# AD8307.net
KiCad netlist of a schematic drawn in Altium Designer
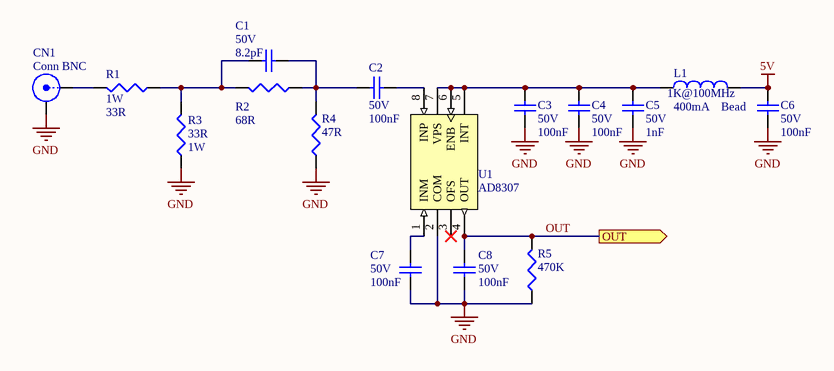
[diagram p0: AD8307.SchDoc]

(export (version "E")
  (design (tool "Eeschema 10.0.6"))
  (components
    (comp (ref "C1")
      (value "8.2pF")
      (footprint "CC0603")
      (description "Capacitor (Semiconductor SIM Model)")
      (fields (field (name "TENSÃO") "50V") (field (name "Comment") "Capacitor Cerâmico"))
      (libsource (lib "NavarroCAP") (part "Cap 8.2nF 50V 0603 X7R"))
    )
    (comp (ref "C2")
      (value "100nF")
      (footprint "CC0603")
      (description "Capacitor (Semiconductor SIM Model)")
      (fields (field (name "TENSÃO") "50V") (field (name "Comment") "Capacitor Cerâmico"))
      (libsource (lib "NavarroCAP") (part "Cap 100nF 50V 0603 X7R"))
    )
    (comp (ref "C3")
      (value "100nF")
      (footprint "CC0603")
      (description "Capacitor (Semiconductor SIM Model)")
      (fields (field (name "TENSÃO") "50V") (field (name "Comment") "Capacitor Cerâmico"))
      (libsource (lib "NavarroCAP") (part "Cap 100nF 50V 0603 X7R"))
    )
    (comp (ref "C4")
      (value "100nF")
      (footprint "CC0603")
      (description "Capacitor (Semiconductor SIM Model)")
      (fields (field (name "TENSÃO") "50V") (field (name "Comment") "Capacitor Cerâmico"))
      (libsource (lib "NavarroCAP") (part "Cap 100nF 50V 0603 X7R"))
    )
    (comp (ref "C5")
      (value "1nF")
      (footprint "CC0603")
      (description "Capacitor (Semiconductor SIM Model)")
      (fields (field (name "TENSÃO") "50V") (field (name "Comment") "Capacitor Cerâmico"))
      (libsource (lib "NavarroCAP") (part "Cap 1nF 50V 0603 X7R"))
    )
    (comp (ref "C6")
      (value "100nF")
      (footprint "CC0603")
      (description "Capacitor (Semiconductor SIM Model)")
      (fields (field (name "TENSÃO") "50V") (field (name "Comment") "Capacitor Cerâmico"))
      (libsource (lib "NavarroCAP") (part "Cap 100nF 50V 0603 X7R"))
    )
    (comp (ref "C7")
      (value "100nF")
      (footprint "CC0603")
      (description "Capacitor (Semiconductor SIM Model)")
      (fields (field (name "TENSÃO") "50V") (field (name "Comment") "Capacitor Cerâmico"))
      (libsource (lib "NavarroCAP") (part "Cap 100nF 50V 0603 X7R"))
    )
    (comp (ref "C8")
      (value "100nF")
      (footprint "CC0603")
      (description "Capacitor (Semiconductor SIM Model)")
      (fields (field (name "TENSÃO") "50V") (field (name "Comment") "Capacitor Cerâmico"))
      (libsource (lib "NavarroCAP") (part "Cap 100nF 50V 0603 X7R"))
    )
    (comp (ref "CN1")
      (value "Conn BNC")
      (footprint "CONN BNC-JACK-TE-5-1634556-0")
      (description "Conector BNC")
      (libsource (lib "TecnocladeCON") (part "Conn BNC"))
    )
    (comp (ref "L1")
      (value "Bead")
      (footprint "CC0603")
      (fields (field (name "CORRENTE") "400mA") (field (name "ALTIUM_VALUE") "1K@100MHz"))
      (libsource (lib "NavarroIND") (part "Bd 1K@100MHz 0603 400mA"))
    )
    (comp (ref "R1")
      (value "33R")
      (footprint "CC2512")
      (description "Resistor")
      (fields (field (name "POTÊNCIA") "1W"))
      (libsource (lib "NavarroRES") (part "Res 33R 1% 0603 1/10W"))
    )
    (comp (ref "R2")
      (value "68R")
      (footprint "CC0603")
      (description "Resistor")
      (libsource (lib "NavarroRES") (part "Res 1K 1% 0603 1/10W"))
    )
    (comp (ref "R3")
      (value "33R")
      (footprint "CC2512")
      (description "Resistor")
      (fields (field (name "POTÊNCIA") "1W"))
      (libsource (lib "NavarroRES") (part "Res 33R 1% 0603 1/10W"))
    )
    (comp (ref "R4")
      (value "47R")
      (footprint "CC0603")
      (description "Resistor")
      (libsource (lib "NavarroRES") (part "Res 1K 1% 0603 1/10W"))
    )
    (comp (ref "R5")
      (value "470K")
      (footprint "CC0603")
      (description "Resistor")
      (libsource (lib "NavarroRES") (part "Res 470K 1% 0603 1/10W"))
    )
    (comp (ref "U1")
      (value "AD8307")
      (footprint "SOIC-8N")
      (description "Low Cost, DC to 500 MHz, 92 dB Log Amp")
      (libsource (lib "Navarro") (part "AD8307"))
    )
  )
  (nets
    (net (code "1") (name "/OUT") (class "Default")
      (node (ref "C8") (pin "2") (pinfunction "2_2") (pintype "passive"))
      (node (ref "R5") (pin "2") (pinfunction "2_2") (pintype "passive"))
      (node (ref "U1") (pin "4") (pinfunction "OUT_4") (pintype "output"))
    )
    (net (code "2") (name "5V") (class "Default")
      (node (ref "C6") (pin "2") (pinfunction "2_2") (pintype "passive"))
      (node (ref "L1") (pin "2") (pinfunction "2_2") (pintype "passive"))
    )
    (net (code "3") (name "GND") (class "Default")
      (node (ref "C3") (pin "1") (pinfunction "1_1") (pintype "passive"))
      (node (ref "C4") (pin "1") (pinfunction "1_1") (pintype "passive"))
      (node (ref "C5") (pin "1") (pinfunction "1_1") (pintype "passive"))
      (node (ref "C6") (pin "1") (pinfunction "1_1") (pintype "passive"))
      (node (ref "C7") (pin "1") (pinfunction "1_1") (pintype "passive"))
      (node (ref "C8") (pin "1") (pinfunction "1_1") (pintype "passive"))
      (node (ref "CN1") (pin "2") (pinfunction "Y_2") (pintype "passive"))
      (node (ref "R3") (pin "1") (pinfunction "1_1") (pintype "passive"))
      (node (ref "R4") (pin "1") (pinfunction "1_1") (pintype "passive"))
      (node (ref "R5") (pin "1") (pinfunction "1_1") (pintype "passive"))
      (node (ref "U1") (pin "2") (pinfunction "COM_2") (pintype "power_in"))
    )
    (net (code "4") (name "Net-(C1-Pad1)") (class "Default")
      (node (ref "C1") (pin "1") (pinfunction "1_1") (pintype "passive"))
      (node (ref "R1") (pin "1") (pinfunction "1_1") (pintype "passive"))
      (node (ref "R2") (pin "2") (pinfunction "2_2") (pintype "passive"))
      (node (ref "R3") (pin "2") (pinfunction "2_2") (pintype "passive"))
    )
    (net (code "5") (name "Net-(C1-Pad2)") (class "Default")
      (node (ref "C1") (pin "2") (pinfunction "2_2") (pintype "passive"))
      (node (ref "C2") (pin "1") (pinfunction "1_1") (pintype "passive"))
      (node (ref "R2") (pin "1") (pinfunction "1_1") (pintype "passive"))
      (node (ref "R4") (pin "2") (pinfunction "2_2") (pintype "passive"))
    )
    (net (code "6") (name "Net-(CN1-X)") (class "Default")
      (node (ref "CN1") (pin "1") (pinfunction "X_1") (pintype "passive"))
      (node (ref "R1") (pin "2") (pinfunction "2_2") (pintype "passive"))
    )
    (net (code "7") (name "Net-(U1-ENB)") (class "Default")
      (node (ref "C3") (pin "2") (pinfunction "2_2") (pintype "passive"))
      (node (ref "C4") (pin "2") (pinfunction "2_2") (pintype "passive"))
      (node (ref "C5") (pin "2") (pinfunction "2_2") (pintype "passive"))
      (node (ref "L1") (pin "1") (pinfunction "1_1") (pintype "passive"))
      (node (ref "U1") (pin "5") (pinfunction "INT_5") (pintype "passive"))
      (node (ref "U1") (pin "6") (pinfunction "ENB_6") (pintype "input"))
      (node (ref "U1") (pin "7") (pinfunction "VPS_7") (pintype "power_in"))
    )
    (net (code "8") (name "Net-(U1-INM)") (class "Default")
      (node (ref "C7") (pin "2") (pinfunction "2_2") (pintype "passive"))
      (node (ref "U1") (pin "1") (pinfunction "INM_1") (pintype "input"))
    )
    (net (code "9") (name "Net-(U1-INP)") (class "Default")
      (node (ref "C2") (pin "2") (pinfunction "2_2") (pintype "passive"))
      (node (ref "U1") (pin "8") (pinfunction "INP_8") (pintype "input"))
    )
    (net (code "10") (name "unconnected-(U1-OFS-Pad3)") (class "Default")
      (node (ref "U1") (pin "3") (pinfunction "OFS_3") (pintype "passive+no_connect"))
    )
  )
)
